# circuit_2.net
KiCad netlist of a schematic drawn in Altium Designer
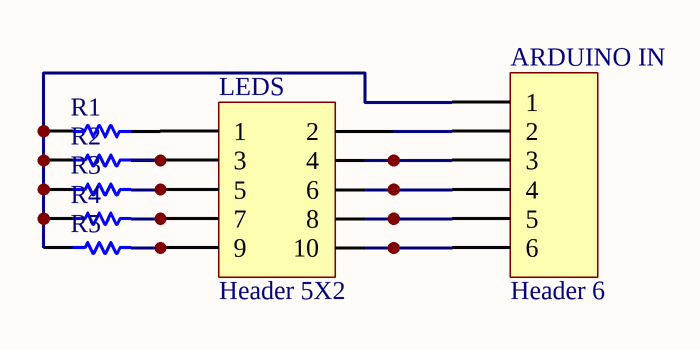
[diagram p0: circuit_2.SchDoc]

(export (version "E")
  (design (tool "Eeschema 10.0.6"))
  (components
    (comp (ref "ARDUINO IN")
      (value "Header 6")
      (footprint "HDR1X6")
      (description "Header, 6-Pin")
      (fields (field (name "PUBLISHER") "Altium Limited"))
      (libsource (lib "Miscellaneous Connectors") (part "Header 6"))
    )
    (comp (ref "LEDS")
      (value "Header 5X2")
      (footprint "HDR2X5")
      (description "Header, 5-Pin, Dual row")
      (fields (field (name "PUBLISHER") "Altium Limited"))
      (libsource (lib "Miscellaneous Connectors") (part "Header 5X2"))
    )
    (comp (ref "R1")
      (value "Res1")
      (footprint "AXIAL-0.3")
      (description "Resistor")
      (fields (field (name "PUBLISHER") "Altium Limited"))
      (libsource (lib "Miscellaneous Devices") (part "Res1"))
    )
    (comp (ref "R2")
      (value "Res1")
      (footprint "AXIAL-0.3")
      (description "Resistor")
      (fields (field (name "PUBLISHER") "Altium Limited"))
      (libsource (lib "Miscellaneous Devices") (part "Res1"))
    )
    (comp (ref "R3")
      (value "Res1")
      (footprint "AXIAL-0.3")
      (description "Resistor")
      (fields (field (name "PUBLISHER") "Altium Limited"))
      (libsource (lib "Miscellaneous Devices") (part "Res1"))
    )
    (comp (ref "R4")
      (value "Res1")
      (footprint "AXIAL-0.3")
      (description "Resistor")
      (fields (field (name "PUBLISHER") "Altium Limited"))
      (libsource (lib "Miscellaneous Devices") (part "Res1"))
    )
    (comp (ref "R5")
      (value "Res1")
      (footprint "AXIAL-0.3")
      (description "Resistor")
      (fields (field (name "PUBLISHER") "Altium Limited"))
      (libsource (lib "Miscellaneous Devices") (part "Res1"))
    )
  )
  (nets
    (net (code "1") (name "Net-(ARDUINO IN-Pad1)") (class "Default")
      (node (ref "ARDUINO IN") (pin "1") (pinfunction "1_1") (pintype "passive"))
      (node (ref "R1") (pin "2") (pinfunction "2_2") (pintype "passive"))
      (node (ref "R2") (pin "1") (pinfunction "1_1") (pintype "passive"))
      (node (ref "R3") (pin "1") (pinfunction "1_1") (pintype "passive"))
      (node (ref "R4") (pin "1") (pinfunction "1_1") (pintype "passive"))
      (node (ref "R5") (pin "1") (pinfunction "1_1") (pintype "passive"))
    )
    (net (code "2") (name "Net-(ARDUINO IN-Pad2)") (class "Default")
      (node (ref "ARDUINO IN") (pin "2") (pinfunction "2_2") (pintype "passive"))
      (node (ref "LEDS") (pin "2") (pinfunction "2_2") (pintype "passive"))
    )
    (net (code "3") (name "Net-(ARDUINO IN-Pad3)") (class "Default")
      (node (ref "ARDUINO IN") (pin "3") (pinfunction "3_3") (pintype "passive"))
      (node (ref "LEDS") (pin "4") (pinfunction "4_4") (pintype "passive"))
    )
    (net (code "4") (name "Net-(ARDUINO IN-Pad4)") (class "Default")
      (node (ref "ARDUINO IN") (pin "4") (pinfunction "4_4") (pintype "passive"))
      (node (ref "LEDS") (pin "6") (pinfunction "6_6") (pintype "passive"))
    )
    (net (code "5") (name "Net-(ARDUINO IN-Pad5)") (class "Default")
      (node (ref "ARDUINO IN") (pin "5") (pinfunction "5_5") (pintype "passive"))
      (node (ref "LEDS") (pin "8") (pinfunction "8_8") (pintype "passive"))
    )
    (net (code "6") (name "Net-(ARDUINO IN-Pad6)") (class "Default")
      (node (ref "ARDUINO IN") (pin "6") (pinfunction "6_6") (pintype "passive"))
      (node (ref "LEDS") (pin "10") (pinfunction "10_10") (pintype "passive"))
    )
    (net (code "7") (name "Net-(LEDS-Pad1)") (class "Default")
      (node (ref "LEDS") (pin "1") (pinfunction "1_1") (pintype "passive"))
      (node (ref "R1") (pin "1") (pinfunction "1_1") (pintype "passive"))
    )
    (net (code "8") (name "Net-(LEDS-Pad3)") (class "Default")
      (node (ref "LEDS") (pin "3") (pinfunction "3_3") (pintype "passive"))
      (node (ref "R2") (pin "2") (pinfunction "2_2") (pintype "passive"))
    )
    (net (code "9") (name "Net-(LEDS-Pad5)") (class "Default")
      (node (ref "LEDS") (pin "5") (pinfunction "5_5") (pintype "passive"))
      (node (ref "R3") (pin "2") (pinfunction "2_2") (pintype "passive"))
    )
    (net (code "10") (name "Net-(LEDS-Pad7)") (class "Default")
      (node (ref "LEDS") (pin "7") (pinfunction "7_7") (pintype "passive"))
      (node (ref "R4") (pin "2") (pinfunction "2_2") (pintype "passive"))
    )
    (net (code "11") (name "Net-(LEDS-Pad9)") (class "Default")
      (node (ref "LEDS") (pin "9") (pinfunction "9_9") (pintype "passive"))
      (node (ref "R5") (pin "2") (pinfunction "2_2") (pintype "passive"))
    )
  )
)
